# 04-Intel_CPLD_1.net
KiCad netlist of a schematic drawn in Altium Designer
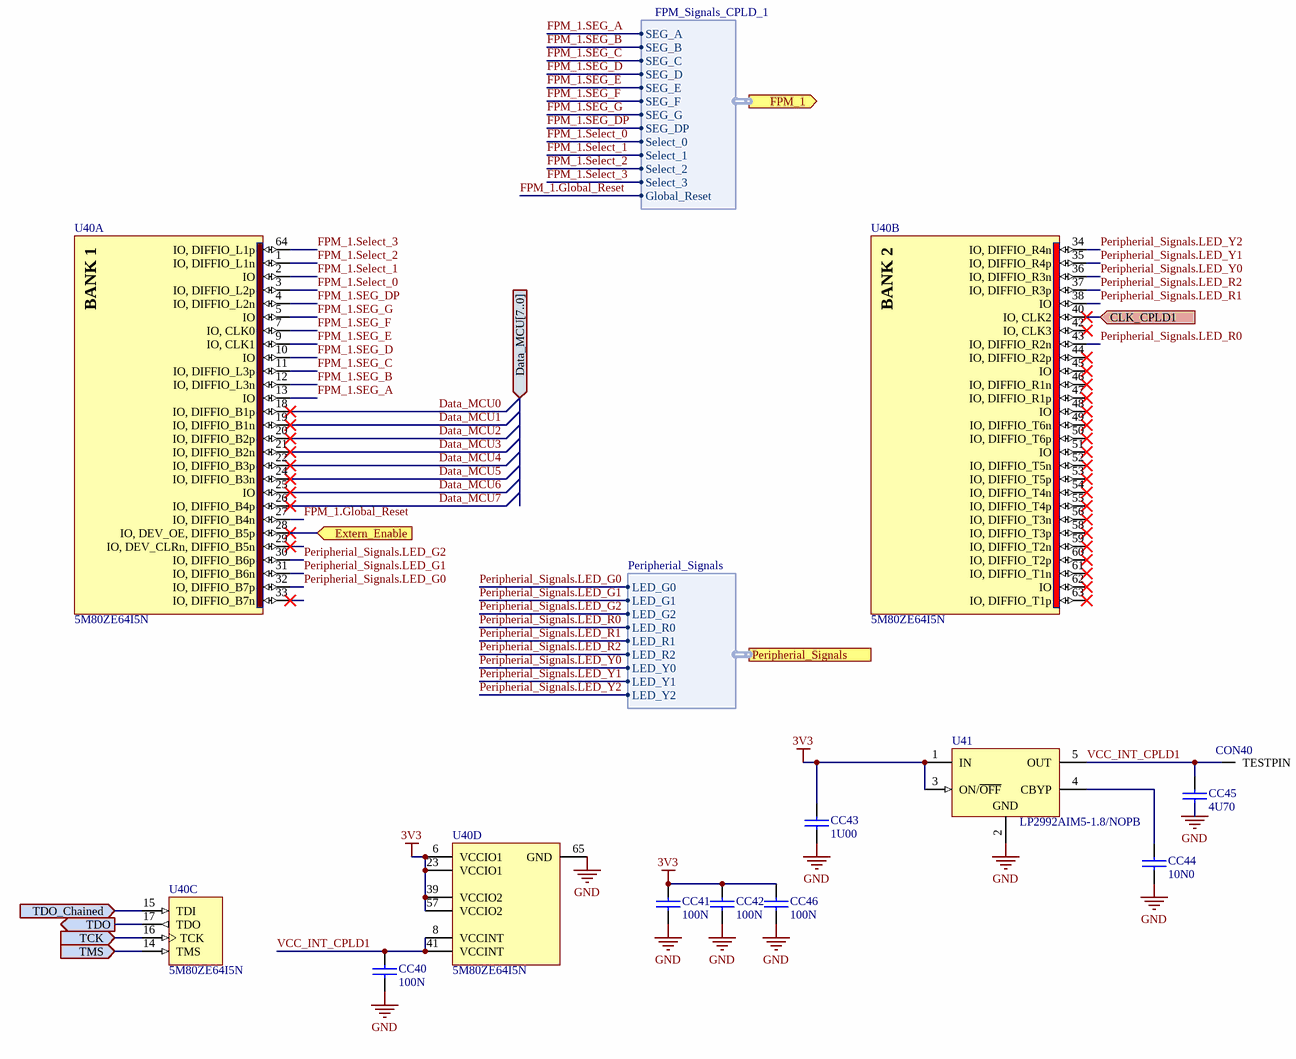
[diagram p0: 04-Intel_CPLD_1.SchDoc]

(export (version "E")
  (design (tool "Eeschema 10.0.6"))
  (components
    (comp (ref "CC40")
      (value "CC")
      (footprint "0603_C")
      (fields
        (field (name "CAPACITANCE") "100N")
        (field (name "MANUFACTURER") "Yageo")
        (field (name "TOLERANCE") "10P0")
      )
      (libsource (lib "Bauteildb") (part "CC"))
    )
    (comp (ref "CC41")
      (value "CC")
      (footprint "0603_C")
      (fields
        (field (name "CAPACITANCE") "100N")
        (field (name "MANUFACTURER") "Yageo")
        (field (name "TOLERANCE") "10P0")
      )
      (libsource (lib "Bauteildb") (part "CC"))
    )
    (comp (ref "CC42")
      (value "CC")
      (footprint "0603_C")
      (fields
        (field (name "CAPACITANCE") "100N")
        (field (name "MANUFACTURER") "Yageo")
        (field (name "TOLERANCE") "10P0")
      )
      (libsource (lib "Bauteildb") (part "CC"))
    )
    (comp (ref "CC43")
      (value "CC")
      (footprint "0603_C")
      (fields
        (field (name "CAPACITANCE") "1U00")
        (field (name "MANUFACTURER") "Taiyo Yuden")
        (field (name "TOLERANCE") "10P0")
      )
      (libsource (lib "Bauteildb") (part "CC"))
    )
    (comp (ref "CC44")
      (value "CC")
      (footprint "0603_C")
      (fields
        (field (name "CAPACITANCE") "10N0")
        (field (name "MANUFACTURER") "Kemet")
        (field (name "TOLERANCE") "10P0")
      )
      (libsource (lib "Bauteildb") (part "CC"))
    )
    (comp (ref "CC45")
      (value "CC")
      (footprint "0603_C")
      (fields
        (field (name "CAPACITANCE") "4U70")
        (field (name "MANUFACTURER") "Samsung")
        (field (name "TOLERANCE") "10P0")
      )
      (libsource (lib "Bauteildb") (part "CC"))
    )
    (comp (ref "CC46")
      (value "CC")
      (footprint "0603_C")
      (fields
        (field (name "CAPACITANCE") "100N")
        (field (name "MANUFACTURER") "Yageo")
        (field (name "TOLERANCE") "10P0")
      )
      (libsource (lib "Bauteildb") (part "CC"))
    )
    (comp (ref "CON40")
      (value "CON_001_M_MM000_S_X_MILL-MAX_TP")
      (footprint "CON_001_THT_MM000_S_D")
      (description "MILL-MAX_TP")
      (fields (field (name "MANUFACTURER") "MILL-MAX") (field (name "EDITOR_DATE") "boos, 06.02.2014"))
      (libsource (lib "Bauteildb") (part "CON_001_M_MM000_S_X_MILL-MAX_TP"))
    )
    (comp (ref "U40")
      (value "5M80ZE64I5N")
      (footprint "EQFP64_A-120_D2-45_M")
      (libsource (lib "Altium Content Vault") (part "PLD-ALMAX5-5M80Z-SQ64"))
    )
    (comp (ref "U41")
      (value "LP2992AIM5-1.8/NOPB")
      (footprint "MF05A_N")
      (description "Micropower 250 mA Low-Noise Ultra Low-Dropout Regulator, 5-pin SOT-23, Pb-Free")
      (fields (field (name "MANUFACTURER") "National Semiconductor"))
      (libsource (lib "Altium Content Vault") (part "PM-REG-LP2985-SOT5"))
    )
  )
  (nets
    (net (code "3") (name "/CLK_CPLD1") (class "Default")
      (node (ref "U40") (pin "40") (pinfunction "IO,_CLK2_40") (pintype "bidirectional+no_connect"))
    )
    (net (code "4") (name "/Data_MCU0") (class "Default")
      (node (ref "U40") (pin "18") (pinfunction "IO,_DIFFIO_B1p_18") (pintype "bidirectional+no_connect"))
    )
    (net (code "5") (name "/Data_MCU1") (class "Default")
      (node (ref "U40") (pin "19") (pinfunction "IO,_DIFFIO_B1n_19") (pintype "bidirectional+no_connect"))
    )
    (net (code "6") (name "/Data_MCU2") (class "Default")
      (node (ref "U40") (pin "20") (pinfunction "IO,_DIFFIO_B2p_20") (pintype "bidirectional+no_connect"))
    )
    (net (code "7") (name "/Data_MCU3") (class "Default")
      (node (ref "U40") (pin "21") (pinfunction "IO,_DIFFIO_B2n_21") (pintype "bidirectional+no_connect"))
    )
    (net (code "8") (name "/Data_MCU4") (class "Default")
      (node (ref "U40") (pin "22") (pinfunction "IO,_DIFFIO_B3p_22") (pintype "bidirectional+no_connect"))
    )
    (net (code "9") (name "/Data_MCU5") (class "Default")
      (node (ref "U40") (pin "24") (pinfunction "IO,_DIFFIO_B3n_24") (pintype "bidirectional+no_connect"))
    )
    (net (code "10") (name "/Data_MCU6") (class "Default")
      (node (ref "U40") (pin "25") (pinfunction "IO_25") (pintype "bidirectional+no_connect"))
    )
    (net (code "11") (name "/Data_MCU7") (class "Default")
      (node (ref "U40") (pin "26") (pinfunction "IO,_DIFFIO_B4p_26") (pintype "bidirectional+no_connect"))
    )
    (net (code "13") (name "/Extern_Enable") (class "Default")
      (node (ref "U40") (pin "28") (pinfunction "IO,_DEV_OE,_DIFFIO_B5p_28") (pintype "bidirectional+no_connect"))
    )
    (net (code "14") (name "/FPM_1.Global_Reset") (class "Default")
      (node (ref "U40") (pin "27") (pinfunction "IO,_DIFFIO_B4n_27") (pintype "bidirectional"))
    )
    (net (code "15") (name "/FPM_1.SEG_A") (class "Default")
      (node (ref "U40") (pin "13") (pinfunction "IO_13") (pintype "bidirectional"))
    )
    (net (code "16") (name "/FPM_1.SEG_B") (class "Default")
      (node (ref "U40") (pin "12") (pinfunction "IO,_DIFFIO_L3n_12") (pintype "bidirectional"))
    )
    (net (code "17") (name "/FPM_1.SEG_C") (class "Default")
      (node (ref "U40") (pin "11") (pinfunction "IO,_DIFFIO_L3p_11") (pintype "bidirectional"))
    )
    (net (code "18") (name "/FPM_1.SEG_D") (class "Default")
      (node (ref "U40") (pin "10") (pinfunction "IO_10") (pintype "bidirectional"))
    )
    (net (code "19") (name "/FPM_1.SEG_DP") (class "Default")
      (node (ref "U40") (pin "4") (pinfunction "IO,_DIFFIO_L2n_4") (pintype "bidirectional"))
    )
    (net (code "20") (name "/FPM_1.SEG_E") (class "Default")
      (node (ref "U40") (pin "9") (pinfunction "IO,_CLK1_9") (pintype "bidirectional"))
    )
    (net (code "21") (name "/FPM_1.SEG_F") (class "Default")
      (node (ref "U40") (pin "7") (pinfunction "IO,_CLK0_7") (pintype "bidirectional"))
    )
    (net (code "22") (name "/FPM_1.SEG_G") (class "Default")
      (node (ref "U40") (pin "5") (pinfunction "IO_5") (pintype "bidirectional"))
    )
    (net (code "23") (name "/FPM_1.Select_0") (class "Default")
      (node (ref "U40") (pin "3") (pinfunction "IO,_DIFFIO_L2p_3") (pintype "bidirectional"))
    )
    (net (code "24") (name "/FPM_1.Select_1") (class "Default")
      (node (ref "U40") (pin "2") (pinfunction "IO_2") (pintype "bidirectional"))
    )
    (net (code "25") (name "/FPM_1.Select_2") (class "Default")
      (node (ref "U40") (pin "1") (pinfunction "IO,_DIFFIO_L1n_1") (pintype "bidirectional"))
    )
    (net (code "26") (name "/FPM_1.Select_3") (class "Default")
      (node (ref "U40") (pin "64") (pinfunction "IO,_DIFFIO_L1p_64") (pintype "bidirectional"))
    )
    (net (code "27") (name "/Peripherial_Signals.LED_G0") (class "Default")
      (node (ref "U40") (pin "32") (pinfunction "IO,_DIFFIO_B7p_32") (pintype "bidirectional"))
    )
    (net (code "28") (name "/Peripherial_Signals.LED_G1") (class "Default")
      (node (ref "U40") (pin "31") (pinfunction "IO,_DIFFIO_B6n_31") (pintype "bidirectional"))
    )
    (net (code "29") (name "/Peripherial_Signals.LED_G2") (class "Default")
      (node (ref "U40") (pin "30") (pinfunction "IO,_DIFFIO_B6p_30") (pintype "bidirectional"))
    )
    (net (code "30") (name "/Peripherial_Signals.LED_R0") (class "Default")
      (node (ref "U40") (pin "43") (pinfunction "IO,_DIFFIO_R2n_43") (pintype "bidirectional"))
    )
    (net (code "31") (name "/Peripherial_Signals.LED_R1") (class "Default")
      (node (ref "U40") (pin "38") (pinfunction "IO_38") (pintype "bidirectional"))
    )
    (net (code "32") (name "/Peripherial_Signals.LED_R2") (class "Default")
      (node (ref "U40") (pin "37") (pinfunction "IO,_DIFFIO_R3p_37") (pintype "bidirectional"))
    )
    (net (code "33") (name "/Peripherial_Signals.LED_Y0") (class "Default")
      (node (ref "U40") (pin "36") (pinfunction "IO,_DIFFIO_R3n_36") (pintype "bidirectional"))
    )
    (net (code "34") (name "/Peripherial_Signals.LED_Y1") (class "Default")
      (node (ref "U40") (pin "35") (pinfunction "IO,_DIFFIO_R4p_35") (pintype "bidirectional"))
    )
    (net (code "35") (name "/Peripherial_Signals.LED_Y2") (class "Default")
      (node (ref "U40") (pin "34") (pinfunction "IO,_DIFFIO_R4n_34") (pintype "bidirectional"))
    )
    (net (code "36") (name "/TCK") (class "Default")
      (node (ref "U40") (pin "16") (pinfunction "TCK_16") (pintype "input"))
    )
    (net (code "37") (name "/TDO") (class "Default")
      (node (ref "U40") (pin "17") (pinfunction "TDO_17") (pintype "output"))
    )
    (net (code "38") (name "/TDO_Chained") (class "Default")
      (node (ref "U40") (pin "15") (pinfunction "TDI_15") (pintype "input"))
    )
    (net (code "39") (name "/TMS") (class "Default")
      (node (ref "U40") (pin "14") (pinfunction "TMS_14") (pintype "input"))
    )
    (net (code "40") (name "/VCC_INT_CPLD1") (class "Default")
      (node (ref "CC40") (pin "2") (pintype "passive"))
      (node (ref "CC45") (pin "2") (pintype "passive"))
      (node (ref "CON40") (pin "1") (pinfunction "TESTPIN_1") (pintype "passive"))
      (node (ref "U40") (pin "41") (pinfunction "VCCINT_41") (pintype "power_in"))
      (node (ref "U40") (pin "8") (pinfunction "VCCINT_8") (pintype "power_in"))
      (node (ref "U41") (pin "5") (pinfunction "OUT_5") (pintype "power_in"))
    )
    (net (code "43") (name "3V3") (class "Default")
      (node (ref "CC41") (pin "2") (pintype "passive"))
      (node (ref "CC42") (pin "2") (pintype "passive"))
      (node (ref "CC43") (pin "2") (pintype "passive"))
      (node (ref "CC46") (pin "2") (pintype "passive"))
      (node (ref "U40") (pin "23") (pinfunction "VCCIO1_23") (pintype "power_in"))
      (node (ref "U40") (pin "39") (pinfunction "VCCIO2_39") (pintype "power_in"))
      (node (ref "U40") (pin "57") (pinfunction "VCCIO2_57") (pintype "power_in"))
      (node (ref "U40") (pin "6") (pinfunction "VCCIO1_6") (pintype "power_in"))
      (node (ref "U41") (pin "1") (pinfunction "IN_1") (pintype "power_in"))
      (node (ref "U41") (pin "3") (pinfunction "ON/~{OFF}_3") (pintype "input"))
    )
    (net (code "44") (name "GND") (class "Default")
      (node (ref "CC40") (pin "1") (pintype "passive"))
      (node (ref "CC41") (pin "1") (pintype "passive"))
      (node (ref "CC42") (pin "1") (pintype "passive"))
      (node (ref "CC43") (pin "1") (pintype "passive"))
      (node (ref "CC44") (pin "1") (pintype "passive"))
      (node (ref "CC45") (pin "1") (pintype "passive"))
      (node (ref "CC46") (pin "1") (pintype "passive"))
      (node (ref "U40") (pin "65") (pinfunction "GND_65") (pintype "power_in"))
      (node (ref "U41") (pin "2") (pinfunction "GND_2") (pintype "power_in"))
    )
    (net (code "45") (name "Net-(U41-CBYP)") (class "Default")
      (node (ref "CC44") (pin "2") (pintype "passive"))
      (node (ref "U41") (pin "4") (pinfunction "CBYP_4") (pintype "passive"))
    )
    (net (code "46") (name "unconnected-(U40A-IO,_DEV_CLRn,_DIFFIO_B5n-Pad29)") (class "Default")
      (node (ref "U40") (pin "29") (pinfunction "IO,_DEV_CLRn,_DIFFIO_B5n_29") (pintype "bidirectional+no_connect"))
    )
    (net (code "47") (name "unconnected-(U40A-IO,_DIFFIO_B7n-Pad33)") (class "Default")
      (node (ref "U40") (pin "33") (pinfunction "IO,_DIFFIO_B7n_33") (pintype "bidirectional+no_connect"))
    )
    (net (code "48") (name "unconnected-(U40B-IO,_CLK3-Pad42)") (class "Default")
      (node (ref "U40") (pin "42") (pinfunction "IO,_CLK3_42") (pintype "bidirectional+no_connect"))
    )
    (net (code "49") (name "unconnected-(U40B-IO,_DIFFIO_R1n-Pad46)") (class "Default")
      (node (ref "U40") (pin "46") (pinfunction "IO,_DIFFIO_R1n_46") (pintype "bidirectional+no_connect"))
    )
    (net (code "50") (name "unconnected-(U40B-IO,_DIFFIO_R1p-Pad47)") (class "Default")
      (node (ref "U40") (pin "47") (pinfunction "IO,_DIFFIO_R1p_47") (pintype "bidirectional+no_connect"))
    )
    (net (code "51") (name "unconnected-(U40B-IO,_DIFFIO_R2p-Pad44)") (class "Default")
      (node (ref "U40") (pin "44") (pinfunction "IO,_DIFFIO_R2p_44") (pintype "bidirectional+no_connect"))
    )
    (net (code "52") (name "unconnected-(U40B-IO,_DIFFIO_T1n-Pad61)") (class "Default")
      (node (ref "U40") (pin "61") (pinfunction "IO,_DIFFIO_T1n_61") (pintype "bidirectional+no_connect"))
    )
    (net (code "53") (name "unconnected-(U40B-IO,_DIFFIO_T1p-Pad63)") (class "Default")
      (node (ref "U40") (pin "63") (pinfunction "IO,_DIFFIO_T1p_63") (pintype "bidirectional+no_connect"))
    )
    (net (code "54") (name "unconnected-(U40B-IO,_DIFFIO_T2n-Pad59)") (class "Default")
      (node (ref "U40") (pin "59") (pinfunction "IO,_DIFFIO_T2n_59") (pintype "bidirectional+no_connect"))
    )
    (net (code "55") (name "unconnected-(U40B-IO,_DIFFIO_T2p-Pad60)") (class "Default")
      (node (ref "U40") (pin "60") (pinfunction "IO,_DIFFIO_T2p_60") (pintype "bidirectional+no_connect"))
    )
    (net (code "56") (name "unconnected-(U40B-IO,_DIFFIO_T3n-Pad56)") (class "Default")
      (node (ref "U40") (pin "56") (pinfunction "IO,_DIFFIO_T3n_56") (pintype "bidirectional+no_connect"))
    )
    (net (code "57") (name "unconnected-(U40B-IO,_DIFFIO_T3p-Pad58)") (class "Default")
      (node (ref "U40") (pin "58") (pinfunction "IO,_DIFFIO_T3p_58") (pintype "bidirectional+no_connect"))
    )
    (net (code "58") (name "unconnected-(U40B-IO,_DIFFIO_T4n-Pad54)") (class "Default")
      (node (ref "U40") (pin "54") (pinfunction "IO,_DIFFIO_T4n_54") (pintype "bidirectional+no_connect"))
    )
    (net (code "59") (name "unconnected-(U40B-IO,_DIFFIO_T4p-Pad55)") (class "Default")
      (node (ref "U40") (pin "55") (pinfunction "IO,_DIFFIO_T4p_55") (pintype "bidirectional+no_connect"))
    )
    (net (code "60") (name "unconnected-(U40B-IO,_DIFFIO_T5n-Pad52)") (class "Default")
      (node (ref "U40") (pin "52") (pinfunction "IO,_DIFFIO_T5n_52") (pintype "bidirectional+no_connect"))
    )
    (net (code "61") (name "unconnected-(U40B-IO,_DIFFIO_T5p-Pad53)") (class "Default")
      (node (ref "U40") (pin "53") (pinfunction "IO,_DIFFIO_T5p_53") (pintype "bidirectional+no_connect"))
    )
    (net (code "62") (name "unconnected-(U40B-IO,_DIFFIO_T6n-Pad49)") (class "Default")
      (node (ref "U40") (pin "49") (pinfunction "IO,_DIFFIO_T6n_49") (pintype "bidirectional+no_connect"))
    )
    (net (code "63") (name "unconnected-(U40B-IO,_DIFFIO_T6p-Pad50)") (class "Default")
      (node (ref "U40") (pin "50") (pinfunction "IO,_DIFFIO_T6p_50") (pintype "bidirectional+no_connect"))
    )
    (net (code "64") (name "unconnected-(U40B-IO-Pad45)") (class "Default")
      (node (ref "U40") (pin "45") (pinfunction "IO_45") (pintype "bidirectional+no_connect"))
    )
    (net (code "65") (name "unconnected-(U40B-IO-Pad48)") (class "Default")
      (node (ref "U40") (pin "48") (pinfunction "IO_48") (pintype "bidirectional+no_connect"))
    )
    (net (code "66") (name "unconnected-(U40B-IO-Pad51)") (class "Default")
      (node (ref "U40") (pin "51") (pinfunction "IO_51") (pintype "bidirectional+no_connect"))
    )
    (net (code "67") (name "unconnected-(U40B-IO-Pad62)") (class "Default")
      (node (ref "U40") (pin "62") (pinfunction "IO_62") (pintype "bidirectional+no_connect"))
    )
  )
)
